# EEG_Schematic.net
KiCad netlist of a schematic drawn in Altium Designer
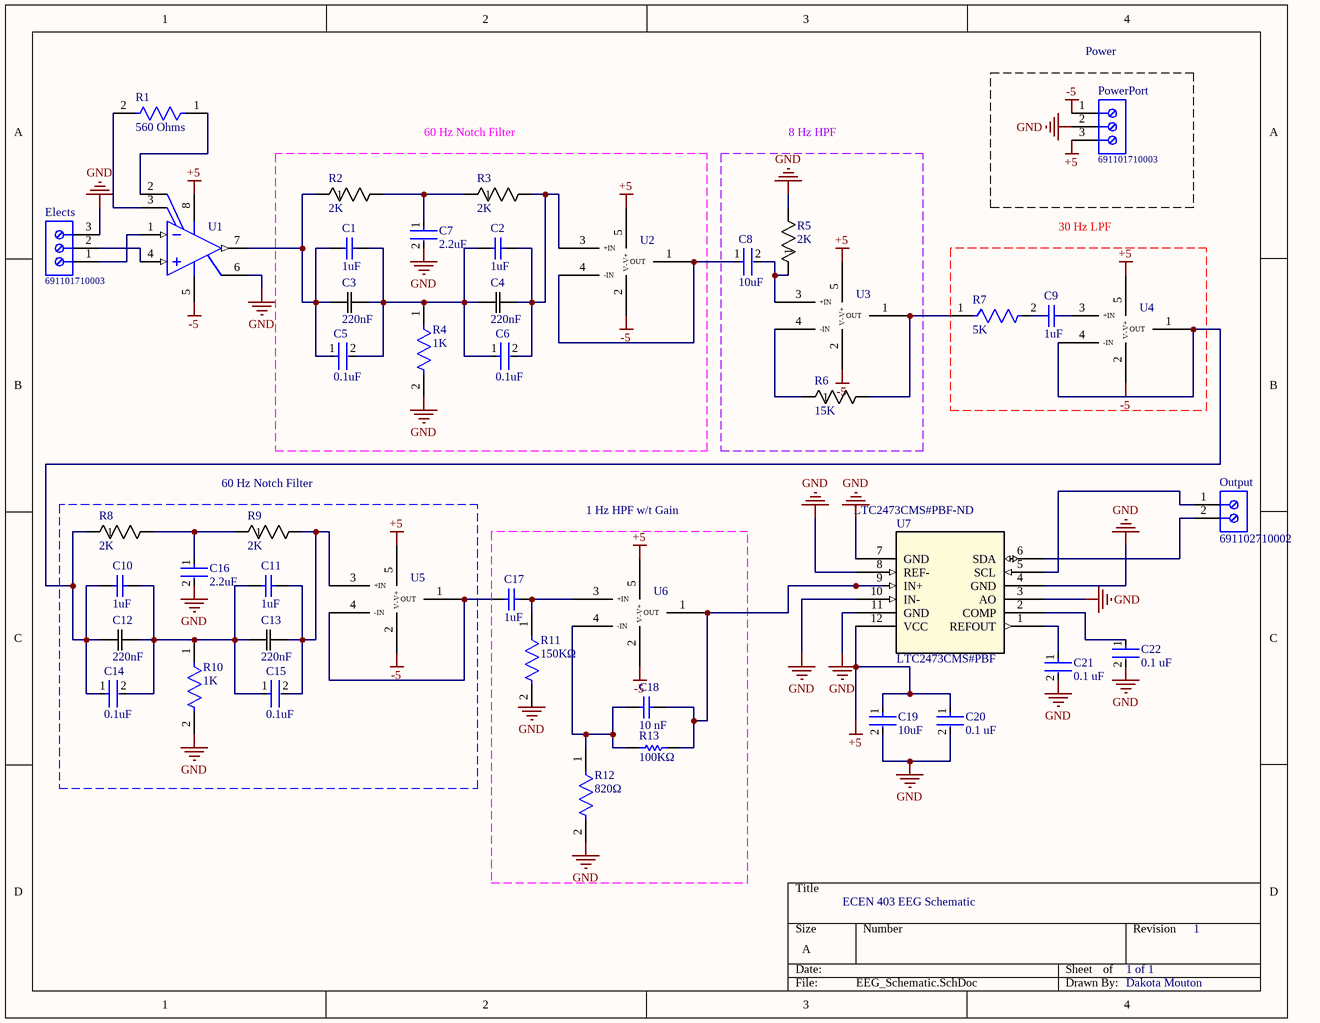
[diagram p0: EEG_Schematic.SchDoc]

(export (version "E")
  (design (tool "Eeschema 10.0.6"))
  (components
    (comp (ref "C1")
      (value "1uF")
      (footprint "CAPC1608X90X35LL15T15")
      (fields (field (name "PART NUMBER") "C0603C105K9PACTU") (field (name "MANUFACTURER") "Kemet"))
      (libsource (lib "Altium Content Vault") (part "CAP"))
    )
    (comp (ref "C2")
      (value "1uF")
      (footprint "CAPC1608X90X35LL15T15")
      (fields (field (name "PART NUMBER") "C0603C105K9PACTU") (field (name "MANUFACTURER") "Kemet"))
      (libsource (lib "Altium Content Vault") (part "CAP"))
    )
    (comp (ref "C3")
      (value "220nF")
      (footprint "CAP_CL05_SAM")
      (description "No Description Available")
      (fields
        (field (name "MANUFACTURER_PART_NUMBER") "CL05B224KO5NNNC")
        (field (name "COPYRIGHT") "Copyright (C) 2021 Ultra Librarian. All rights reserved.")
      )
      (libsource (lib "CL05B224KO5NNNC") (part "CL05B224KO5NNNC"))
    )
    (comp (ref "C4")
      (value "220nF")
      (footprint "CAP_CL05_SAM")
      (description "No Description Available")
      (fields
        (field (name "MANUFACTURER_PART_NUMBER") "CL05B224KO5NNNC")
        (field (name "COPYRIGHT") "Copyright (C) 2021 Ultra Librarian. All rights reserved.")
      )
      (libsource (lib "CL05B224KO5NNNC") (part "CL05B224KO5NNNC"))
    )
    (comp (ref "C5")
      (value "0.1uF")
      (footprint "FP-CL278-IPC_C")
      (description "Cap Ceramic 100nF 25V X5R ±10% SMD 0402 +85°C Paper T/R")
      (fields (field (name "VOLTAGE") "25V") (field (name "TOLERANCE") "10%"))
      (libsource (lib "Altium Content Vault") (part "b4654b650e69147ec39a6b967a45e02"))
    )
    (comp (ref "C6")
      (value "0.1uF")
      (footprint "FP-CL278-IPC_C")
      (description "Cap Ceramic 100nF 25V X5R ±10% SMD 0402 +85°C Paper T/R")
      (fields (field (name "VOLTAGE") "25V") (field (name "TOLERANCE") "10%"))
      (libsource (lib "Altium Content Vault") (part "b4654b650e69147ec39a6b967a45e02"))
    )
    (comp (ref "C7")
      (value "2.2uF")
      (footprint "FP-CL10-IPC_A")
      (description "Cap Ceramic 2.2uF 10V X7R ±10% Pad SMD 0603 +125°C T/R")
      (fields (field (name "TOLERANCE") "10%"))
      (libsource (lib "Altium Content Vault") (part "b4654b650e69147ec39a6b967a45e02"))
    )
    (comp (ref "C8")
      (value "10uF")
      (footprint "FP-CL21-IPC_C")
      (description "CL21 Series 0805 10uF 10V ±10% Tolerance X5R Multilayer Ceramic Chip Capacitor")
      (fields (field (name "TOLERANCE") "10%"))
      (libsource (lib "Altium Content Vault") (part "b4654b650e69147ec39a6b967a45e02"))
    )
    (comp (ref "C9")
      (value "1uF")
      (footprint "CAPC1608X90X35LL15T15")
      (fields (field (name "PART NUMBER") "C0603C105K9PACTU") (field (name "MANUFACTURER") "Kemet"))
      (libsource (lib "Altium Content Vault") (part "CAP"))
    )
    (comp (ref "C10")
      (value "1uF")
      (footprint "CAPC1608X90X35LL15T15")
      (fields (field (name "PART NUMBER") "C0603C105K9PACTU") (field (name "MANUFACTURER") "Kemet"))
      (libsource (lib "Altium Content Vault") (part "CAP"))
    )
    (comp (ref "C11")
      (value "1uF")
      (footprint "CAPC1608X90X35LL15T15")
      (fields (field (name "PART NUMBER") "C0603C105K9PACTU") (field (name "MANUFACTURER") "Kemet"))
      (libsource (lib "Altium Content Vault") (part "CAP"))
    )
    (comp (ref "C12")
      (value "220nF")
      (footprint "CAP_CL05_SAM")
      (description "No Description Available")
      (fields
        (field (name "MANUFACTURER_PART_NUMBER") "CL05B224KO5NNNC")
        (field (name "COPYRIGHT") "Copyright (C) 2021 Ultra Librarian. All rights reserved.")
      )
      (libsource (lib "CL05B224KO5NNNC") (part "CL05B224KO5NNNC"))
    )
    (comp (ref "C13")
      (value "220nF")
      (footprint "CAP_CL05_SAM")
      (description "No Description Available")
      (fields
        (field (name "MANUFACTURER_PART_NUMBER") "CL05B224KO5NNNC")
        (field (name "COPYRIGHT") "Copyright (C) 2021 Ultra Librarian. All rights reserved.")
      )
      (libsource (lib "CL05B224KO5NNNC") (part "CL05B224KO5NNNC"))
    )
    (comp (ref "C14")
      (value "0.1uF")
      (footprint "FP-CL278-IPC_C")
      (description "Cap Ceramic 100nF 25V X5R ±10% SMD 0402 +85°C Paper T/R")
      (fields (field (name "VOLTAGE") "25V") (field (name "TOLERANCE") "10%"))
      (libsource (lib "Altium Content Vault") (part "b4654b650e69147ec39a6b967a45e02"))
    )
    (comp (ref "C15")
      (value "0.1uF")
      (footprint "FP-CL278-IPC_C")
      (description "Cap Ceramic 100nF 25V X5R ±10% SMD 0402 +85°C Paper T/R")
      (fields (field (name "VOLTAGE") "25V") (field (name "TOLERANCE") "10%"))
      (libsource (lib "Altium Content Vault") (part "b4654b650e69147ec39a6b967a45e02"))
    )
    (comp (ref "C16")
      (value "2.2uF")
      (footprint "FP-CL10-IPC_A")
      (description "Cap Ceramic 2.2uF 10V X7R ±10% Pad SMD 0603 +125°C T/R")
      (fields (field (name "TOLERANCE") "10%"))
      (libsource (lib "Altium Content Vault") (part "b4654b650e69147ec39a6b967a45e02"))
    )
    (comp (ref "C17")
      (value "1uF")
      (footprint "CAPC1608X90X35LL15T15")
      (fields (field (name "PART NUMBER") "C0603C105K9PACTU") (field (name "MANUFACTURER") "Kemet"))
      (libsource (lib "Altium Content Vault") (part "CAP"))
    )
    (comp (ref "C18")
      (value "10 nF")
      (footprint "CAPC1005X56X25NL10T15")
      (fields
        (field (name "PART NUMBER") "0402YC103KAT2A")
        (field (name "MANUFACTURER") "AVX Interconnect / Elco")
      )
      (libsource (lib "Altium Content Vault") (part "CAP"))
    )
    (comp (ref "C19")
      (value "10uF")
      (footprint "FP-CL21-IPC_C")
      (description "CL21 Series 0805 10uF 10V ±10% Tolerance X5R Multilayer Ceramic Chip Capacitor")
      (fields (field (name "TOLERANCE") "10%"))
      (libsource (lib "Altium Content Vault") (part "b4654b650e69147ec39a6b967a45e02"))
    )
    (comp (ref "C20")
      (value "0.1 uF")
      (footprint "FP-CL278-IPC_C")
      (description "Cap Ceramic 100nF 25V X5R ±10% SMD 0402 +85°C Paper T/R")
      (fields (field (name "VOLTAGE") "25V") (field (name "TOLERANCE") "10%"))
      (libsource (lib "Altium Content Vault") (part "b4654b650e69147ec39a6b967a45e02"))
    )
    (comp (ref "C21")
      (value "0.1 uF")
      (footprint "FP-CL278-IPC_C")
      (description "Cap Ceramic 100nF 25V X5R ±10% SMD 0402 +85°C Paper T/R")
      (fields (field (name "VOLTAGE") "25V") (field (name "TOLERANCE") "10%"))
      (libsource (lib "Altium Content Vault") (part "b4654b650e69147ec39a6b967a45e02"))
    )
    (comp (ref "C22")
      (value "0.1 uF")
      (footprint "FP-CL278-IPC_C")
      (description "Cap Ceramic 100nF 25V X5R ±10% SMD 0402 +85°C Paper T/R")
      (fields (field (name "VOLTAGE") "25V") (field (name "TOLERANCE") "10%"))
      (libsource (lib "Altium Content Vault") (part "b4654b650e69147ec39a6b967a45e02"))
    )
    (comp (ref "Elects")
      (value "691101710003")
      (footprint "691101710003")
      (description "Series 101 - 5.00 mm Horizontal Entry Modular with Pressure Clamp WR-TBL, 3 pin")
      (fields (field (name "MANUFACTURER") "Wurth Elektronik") (field (name "PUBLISHER") "WurthElektronik"))
      (libsource (lib "Altium Content Vault") (part "WE-CN-1P-F-TB3"))
    )
    (comp (ref "Output")
      (value "691102710002")
      (footprint "691102710002")
      (description "Series 102 - 5.00 mm Horizontal Entry Modular with Pressure Clamp WR-TBL, 2 pin")
      (fields (field (name "MANUFACTURER") "Wurth Elektronik") (field (name "PUBLISHER") "WurthElektronik"))
      (libsource (lib "Altium Content Vault") (part "WE-CN-1P-F-TB2"))
    )
    (comp (ref "PowerPort")
      (value "691101710003")
      (footprint "691101710003")
      (description "Series 101 - 5.00 mm Horizontal Entry Modular with Pressure Clamp WR-TBL, 3 pin")
      (fields (field (name "MANUFACTURER") "Wurth Elektronik") (field (name "PUBLISHER") "WurthElektronik"))
      (libsource (lib "Altium Content Vault") (part "WE-CN-1P-F-TB3"))
    )
    (comp (ref "R1")
      (value "560 Ohms")
      (footprint "FP-CRGCQ1206-IPC_C")
      (description "CRGCQ 1206 560R 1%")
      (fields
        (field (name "MANUFACTURER PART NUMBER") "CRGCQ1206F560R")
        (field (name "OCTOPART") "https://octopart.com/crgcq1206f560r-te+connectivity-91018289")
      )
      (libsource (lib "Altium Content Vault") (part "1029c3af85768c4190bb7ad29bc67b5"))
    )
    (comp (ref "R2")
      (value "2K")
      (footprint "STA_RNCP0805_STP")
      (description "No Description Available")
      (fields
        (field (name "MANUFACTURER_PART_NUMBER") "RNCP0805FTD2K00")
        (field (name "COPYRIGHT") "Copyright (C) 2021 Ultra Librarian. All rights reserved.")
      )
      (libsource (lib "RNCP0805FTD2K00") (part "RNCP0805FTD2K00"))
    )
    (comp (ref "R3")
      (value "2K")
      (footprint "STA_RNCP0805_STP")
      (description "No Description Available")
      (fields
        (field (name "MANUFACTURER_PART_NUMBER") "RNCP0805FTD2K00")
        (field (name "COPYRIGHT") "Copyright (C) 2021 Ultra Librarian. All rights reserved.")
      )
      (libsource (lib "RNCP0805FTD2K00") (part "RNCP0805FTD2K00"))
    )
    (comp (ref "R4")
      (value "1K")
      (footprint "FP-RNCP0805-MFG")
      (description "1kΩ ±1% 0.25W 0805 High Power Anti-Sulfur Thin Film Chip Resistor")
      (fields (field (name "TOLERANCE") "1%"))
      (libsource (lib "Altium Content Vault") (part "1029c3af85768c4190bb7ad29bc67b5"))
    )
    (comp (ref "R5")
      (value "2K")
      (footprint "STA_RNCP0805_STP")
      (description "No Description Available")
      (fields
        (field (name "MANUFACTURER_PART_NUMBER") "RNCP0805FTD2K00")
        (field (name "COPYRIGHT") "Copyright (C) 2021 Ultra Librarian. All rights reserved.")
      )
      (libsource (lib "RNCP0805FTD2K00") (part "RNCP0805FTD2K00"))
    )
    (comp (ref "R6")
      (value "15K")
      (footprint "STA_RNCP0805_STP")
      (description "No Description Available")
      (fields
        (field (name "MANUFACTURER_PART_NUMBER") "RNCP0805FTD15K0")
        (field (name "COPYRIGHT") "Copyright (C) 2021 Ultra Librarian. All rights reserved.")
      )
      (libsource (lib "RNCP0805FTD15K0") (part "RNCP0805FTD15K0"))
    )
    (comp (ref "R7")
      (value "5K")
      (footprint "FP-RT1206-0_65-MFG")
      (description "RES SMD 5K OHM 0.1% 1/4W 1206")
      (fields
        (field (name "OCTOPART") "https://octopart.com/rt1206brd075kl-yageo-29806230")
        (field (name "MANUFACTURER") "Yageo")
      )
      (libsource (lib "Altium Content Vault") (part "1029c3af85768c4190bb7ad29bc67b5"))
    )
    (comp (ref "R8")
      (value "2K")
      (footprint "STA_RNCP0805_STP")
      (description "No Description Available")
      (fields
        (field (name "MANUFACTURER_PART_NUMBER") "RNCP0805FTD2K00")
        (field (name "COPYRIGHT") "Copyright (C) 2021 Ultra Librarian. All rights reserved.")
      )
      (libsource (lib "RNCP0805FTD2K00") (part "RNCP0805FTD2K00"))
    )
    (comp (ref "R9")
      (value "2K")
      (footprint "STA_RNCP0805_STP")
      (description "No Description Available")
      (fields
        (field (name "MANUFACTURER_PART_NUMBER") "RNCP0805FTD2K00")
        (field (name "COPYRIGHT") "Copyright (C) 2021 Ultra Librarian. All rights reserved.")
      )
      (libsource (lib "RNCP0805FTD2K00") (part "RNCP0805FTD2K00"))
    )
    (comp (ref "R10")
      (value "1K")
      (footprint "FP-RNCP0805-MFG")
      (description "1kΩ ±1% 0.25W 0805 High Power Anti-Sulfur Thin Film Chip Resistor")
      (fields (field (name "TOLERANCE") "1%"))
      (libsource (lib "Altium Content Vault") (part "1029c3af85768c4190bb7ad29bc67b5"))
    )
    (comp (ref "R11")
      (value "150KΩ")
      (footprint "FP-CRGP0603-IPC_C")
      (description "CRGP0603 150KΩ 0.25W ±100ppm/°C 1% 50V")
      (fields
        (field (name "TOLERANCE") "0.01")
        (field (name "OCTOPART") "https://octopart.com/crgp0603f150k-te+connectivity-91018727")
      )
      (libsource (lib "Altium Content Vault") (part "1029c3af85768c4190bb7ad29bc67b5"))
    )
    (comp (ref "R12")
      (value "820Ω")
      (footprint "FP-RMCF1206-IPC_C")
      (description "820Ω ±5% 0.25W 1206 Thick Film Chip Resistor AEC-Q200 compliant")
      (fields (field (name "TOLERANCE") "5%"))
      (libsource (lib "Altium Content Vault") (part "1029c3af85768c4190bb7ad29bc67b5"))
    )
    (comp (ref "R13")
      (value "100KΩ")
      (footprint "RESC2013X60X30NL20T20")
      (fields (field (name "MANUFACTURER") "KOA Speer") (field (name "PART NUMBER") "RK73H2ATTD1003F"))
      (libsource (lib "Altium Content Vault") (part "RES"))
    )
    (comp (ref "U1")
      (value "AD8221BRZ-R7 Instrumentation Amplifier")
      (footprint "ADI-R-8_M")
      (fields (field (name "MANUFACTURER") "Analog Devices") (field (name "PARTNUMBER") "AD8221BRZ-R7"))
      (libsource (lib "Altium Content Vault") (part "ADI-AD8221-8"))
    )
    (comp (ref "U2")
      (value "ADA4610-1ARJZ-R7")
      (footprint "RJ_5_ADI")
      (description "No Description Available")
      (fields (field (name "COPYRIGHT") "Copyright (C) 2021 Ultra Librarian. All rights reserved."))
      (libsource (lib "ADA4610-1ARJZ-R7") (part "ADA4610-1ARJZ-R7"))
    )
    (comp (ref "U3")
      (value "ADA4610-1ARJZ-R7")
      (footprint "RJ_5_ADI")
      (description "No Description Available")
      (fields (field (name "COPYRIGHT") "Copyright (C) 2021 Ultra Librarian. All rights reserved."))
      (libsource (lib "ADA4610-1ARJZ-R7") (part "ADA4610-1ARJZ-R7"))
    )
    (comp (ref "U4")
      (value "ADA4610-1ARJZ-R7")
      (footprint "RJ_5_ADI")
      (description "No Description Available")
      (fields (field (name "COPYRIGHT") "Copyright (C) 2021 Ultra Librarian. All rights reserved."))
      (libsource (lib "ADA4610-1ARJZ-R7") (part "ADA4610-1ARJZ-R7"))
    )
    (comp (ref "U5")
      (value "ADA4610-1ARJZ-R7")
      (footprint "RJ_5_ADI")
      (description "No Description Available")
      (fields (field (name "COPYRIGHT") "Copyright (C) 2021 Ultra Librarian. All rights reserved."))
      (libsource (lib "ADA4610-1ARJZ-R7") (part "ADA4610-1ARJZ-R7"))
    )
    (comp (ref "U6")
      (value "ADA4610-1ARJZ-R7")
      (footprint "RJ_5_ADI")
      (description "No Description Available")
      (fields (field (name "COPYRIGHT") "Copyright (C) 2021 Ultra Librarian. All rights reserved."))
      (libsource (lib "ADA4610-1ARJZ-R7") (part "ADA4610-1ARJZ-R7"))
    )
    (comp (ref "U7")
      (value "LTC2473CMS#PBF")
      (footprint "MSOP-12_MS_LIT")
      (description "No Description Available")
      (fields
        (field (name "SUPPLIER PART NUMBER 1") "LTC2473CMS#PBF-ND")
        (field (name "COPYRIGHT") "Copyright (C) 2021 Ultra Librarian. All rights reserved.")
      )
      (libsource (lib "LTC2473CMS&hash_PBF") (part "LTC2473CMS#PBF"))
    )
  )
  (nets
    (net (code "1") (name "+5") (class "Default")
      (node (ref "C19") (pin "1") (pinfunction "1_1") (pintype "passive"))
      (node (ref "C20") (pin "1") (pinfunction "1_1") (pintype "passive"))
      (node (ref "PowerPort") (pin "3") (pinfunction "3_3") (pintype "passive"))
      (node (ref "U1") (pin "8") (pinfunction "VS+_8") (pintype "power_in"))
      (node (ref "U2") (pin "5") (pinfunction "V+_5") (pintype "power_in"))
      (node (ref "U3") (pin "5") (pinfunction "V+_5") (pintype "power_in"))
      (node (ref "U4") (pin "5") (pinfunction "V+_5") (pintype "power_in"))
      (node (ref "U5") (pin "5") (pinfunction "V+_5") (pintype "power_in"))
      (node (ref "U6") (pin "5") (pinfunction "V+_5") (pintype "power_in"))
      (node (ref "U7") (pin "12") (pinfunction "VCC_12") (pintype "power_in"))
    )
    (net (code "2") (name "-5") (class "Default")
      (node (ref "PowerPort") (pin "1") (pinfunction "1_1") (pintype "passive"))
      (node (ref "U1") (pin "5") (pinfunction "VS-_5") (pintype "power_in"))
      (node (ref "U2") (pin "2") (pinfunction "V-_2") (pintype "power_in"))
      (node (ref "U3") (pin "2") (pinfunction "V-_2") (pintype "power_in"))
      (node (ref "U4") (pin "2") (pinfunction "V-_2") (pintype "power_in"))
      (node (ref "U5") (pin "2") (pinfunction "V-_2") (pintype "power_in"))
      (node (ref "U6") (pin "2") (pinfunction "V-_2") (pintype "power_in"))
    )
    (net (code "3") (name "GND") (class "Default")
      (node (ref "C16") (pin "2") (pinfunction "2_2") (pintype "passive"))
      (node (ref "C19") (pin "2") (pinfunction "2_2") (pintype "passive"))
      (node (ref "C20") (pin "2") (pinfunction "2_2") (pintype "passive"))
      (node (ref "C21") (pin "2") (pinfunction "2_2") (pintype "passive"))
      (node (ref "C22") (pin "2") (pinfunction "2_2") (pintype "passive"))
      (node (ref "C7") (pin "2") (pinfunction "2_2") (pintype "passive"))
      (node (ref "Elects") (pin "3") (pinfunction "3_3") (pintype "passive"))
      (node (ref "PowerPort") (pin "2") (pinfunction "2_2") (pintype "passive"))
      (node (ref "R10") (pin "2") (pinfunction "2_2") (pintype "passive"))
      (node (ref "R12") (pin "2") (pinfunction "2_2") (pintype "passive"))
      (node (ref "R4") (pin "2") (pinfunction "2_2") (pintype "passive"))
      (node (ref "R5") (pin "2") (pinfunction "2_2") (pintype "passive"))
      (node (ref "U1") (pin "6") (pinfunction "REF_6") (pintype "passive"))
      (node (ref "U7") (pin "10") (pinfunction "IN-_10") (pintype "input"))
      (node (ref "U7") (pin "11") (pinfunction "GND_11") (pintype "power_in"))
      (node (ref "U7") (pin "3") (pinfunction "AO_3") (pintype "passive"))
      (node (ref "U7") (pin "4") (pinfunction "GND_4") (pintype "power_in"))
      (node (ref "U7") (pin "7") (pinfunction "GND_7") (pintype "power_in"))
      (node (ref "U7") (pin "8") (pinfunction "REF-_8") (pintype "input"))
    )
    (net (code "4") (name "Net-(C1-Pad2)") (class "Default")
      (node (ref "C1") (pin "2") (pinfunction "2_2") (pintype "passive"))
      (node (ref "C2") (pin "1") (pinfunction "1_1") (pintype "passive"))
      (node (ref "C3") (pin "2") (pinfunction "2_2") (pintype "passive"))
      (node (ref "C4") (pin "1") (pinfunction "1_1") (pintype "passive"))
      (node (ref "C5") (pin "2") (pinfunction "2_2") (pintype "passive"))
      (node (ref "C6") (pin "1") (pinfunction "1_1") (pintype "passive"))
      (node (ref "R4") (pin "1") (pinfunction "1_1") (pintype "passive"))
    )
    (net (code "5") (name "Net-(C7-Pad1)") (class "Default")
      (node (ref "C7") (pin "1") (pinfunction "1_1") (pintype "passive"))
      (node (ref "R2") (pin "2") (pinfunction "2_2") (pintype "passive"))
      (node (ref "R3") (pin "1") (pinfunction "1_1") (pintype "passive"))
    )
    (net (code "6") (name "Net-(C9-Pad1)") (class "Default")
      (node (ref "C9") (pin "1") (pinfunction "1_1") (pintype "passive"))
      (node (ref "R7") (pin "2") (pinfunction "2_2") (pintype "passive"))
    )
    (net (code "7") (name "Net-(C10-Pad2)") (class "Default")
      (node (ref "C10") (pin "2") (pinfunction "2_2") (pintype "passive"))
      (node (ref "C11") (pin "1") (pinfunction "1_1") (pintype "passive"))
      (node (ref "C12") (pin "2") (pinfunction "2_2") (pintype "passive"))
      (node (ref "C13") (pin "1") (pinfunction "1_1") (pintype "passive"))
      (node (ref "C14") (pin "2") (pinfunction "2_2") (pintype "passive"))
      (node (ref "C15") (pin "1") (pinfunction "1_1") (pintype "passive"))
      (node (ref "R10") (pin "1") (pinfunction "1_1") (pintype "passive"))
    )
    (net (code "8") (name "Net-(C16-Pad1)") (class "Default")
      (node (ref "C16") (pin "1") (pinfunction "1_1") (pintype "passive"))
      (node (ref "R8") (pin "2") (pinfunction "2_2") (pintype "passive"))
      (node (ref "R9") (pin "1") (pinfunction "1_1") (pintype "passive"))
    )
    (net (code "9") (name "Net-(R1-Pad1)") (class "Default")
      (node (ref "R1") (pin "1") (pinfunction "1_1") (pintype "passive"))
      (node (ref "U1") (pin "2") (pinfunction "RG_2") (pintype "passive"))
    )
    (net (code "10") (name "Net-(R1-Pad2)") (class "Default")
      (node (ref "R1") (pin "2") (pinfunction "2_2") (pintype "passive"))
      (node (ref "U1") (pin "3") (pinfunction "RG_3") (pintype "passive"))
    )
    (net (code "11") (name "Net-(U1-IN+)") (class "Default")
      (node (ref "Elects") (pin "2") (pinfunction "2_2") (pintype "passive"))
      (node (ref "U1") (pin "4") (pinfunction "IN+_4") (pintype "input"))
    )
    (net (code "12") (name "Net-(U1-IN-)") (class "Default")
      (node (ref "Elects") (pin "1") (pinfunction "1_1") (pintype "passive"))
      (node (ref "U1") (pin "1") (pinfunction "IN-_1") (pintype "input"))
    )
    (net (code "13") (name "Net-(U1-VOUT)") (class "Default")
      (node (ref "C1") (pin "1") (pinfunction "1_1") (pintype "passive"))
      (node (ref "C3") (pin "1") (pinfunction "1_1") (pintype "passive"))
      (node (ref "C5") (pin "1") (pinfunction "1_1") (pintype "passive"))
      (node (ref "R2") (pin "1") (pinfunction "1_1") (pintype "passive"))
      (node (ref "U1") (pin "7") (pinfunction "VOUT_7") (pintype "output"))
    )
    (net (code "14") (name "Net-(U2-+IN)") (class "Default")
      (node (ref "C2") (pin "2") (pinfunction "2_2") (pintype "passive"))
      (node (ref "C4") (pin "2") (pinfunction "2_2") (pintype "passive"))
      (node (ref "C6") (pin "2") (pinfunction "2_2") (pintype "passive"))
      (node (ref "R3") (pin "2") (pinfunction "2_2") (pintype "passive"))
      (node (ref "U2") (pin "3") (pinfunction "+IN_3") (pintype "passive"))
    )
    (net (code "15") (name "Net-(U2--IN)") (class "Default")
      (node (ref "C8") (pin "1") (pinfunction "1_1") (pintype "passive"))
      (node (ref "U2") (pin "1") (pinfunction "OUT_1") (pintype "passive"))
      (node (ref "U2") (pin "4") (pinfunction "-IN_4") (pintype "passive"))
    )
    (net (code "16") (name "Net-(U3-+IN)") (class "Default")
      (node (ref "C8") (pin "2") (pinfunction "2_2") (pintype "passive"))
      (node (ref "R5") (pin "1") (pinfunction "1_1") (pintype "passive"))
      (node (ref "U3") (pin "3") (pinfunction "+IN_3") (pintype "passive"))
    )
    (net (code "17") (name "Net-(U3--IN)") (class "Default")
      (node (ref "R6") (pin "1") (pinfunction "1_1") (pintype "passive"))
      (node (ref "U3") (pin "4") (pinfunction "-IN_4") (pintype "passive"))
    )
    (net (code "18") (name "Net-(U3-OUT)") (class "Default")
      (node (ref "R6") (pin "2") (pinfunction "2_2") (pintype "passive"))
      (node (ref "R7") (pin "1") (pinfunction "1_1") (pintype "passive"))
      (node (ref "U3") (pin "1") (pinfunction "OUT_1") (pintype "passive"))
    )
    (net (code "19") (name "Net-(U4-+IN)") (class "Default")
      (node (ref "C9") (pin "2") (pinfunction "2_2") (pintype "passive"))
      (node (ref "U4") (pin "3") (pinfunction "+IN_3") (pintype "passive"))
    )
    (net (code "20") (name "Net-(U4--IN)") (class "Default")
      (node (ref "C10") (pin "1") (pinfunction "1_1") (pintype "passive"))
      (node (ref "C12") (pin "1") (pinfunction "1_1") (pintype "passive"))
      (node (ref "C14") (pin "1") (pinfunction "1_1") (pintype "passive"))
      (node (ref "R8") (pin "1") (pinfunction "1_1") (pintype "passive"))
      (node (ref "U4") (pin "1") (pinfunction "OUT_1") (pintype "passive"))
      (node (ref "U4") (pin "4") (pinfunction "-IN_4") (pintype "passive"))
    )
    (net (code "21") (name "Net-(U5-+IN)") (class "Default")
      (node (ref "C11") (pin "2") (pinfunction "2_2") (pintype "passive"))
      (node (ref "C13") (pin "2") (pinfunction "2_2") (pintype "passive"))
      (node (ref "C15") (pin "2") (pinfunction "2_2") (pintype "passive"))
      (node (ref "R9") (pin "2") (pinfunction "2_2") (pintype "passive"))
      (node (ref "U5") (pin "3") (pinfunction "+IN_3") (pintype "passive"))
    )
    (net (code "22") (name "Net-(U5--IN)") (class "Default")
      (node (ref "C17") (pin "1") (pinfunction "1_1") (pintype "passive"))
      (node (ref "U5") (pin "1") (pinfunction "OUT_1") (pintype "passive"))
      (node (ref "U5") (pin "4") (pinfunction "-IN_4") (pintype "passive"))
    )
    (net (code "23") (name "Net-(U6-+IN)") (class "Default")
      (node (ref "C17") (pin "2") (pinfunction "2_2") (pintype "passive"))
      (node (ref "R11") (pin "1") (pinfunction "1_1") (pintype "passive"))
      (node (ref "U6") (pin "3") (pinfunction "+IN_3") (pintype "passive"))
    )
    (net (code "24") (name "Net-(U6--IN)") (class "Default")
      (node (ref "C18") (pin "1") (pinfunction "1_1") (pintype "passive"))
      (node (ref "R12") (pin "1") (pinfunction "1_1") (pintype "passive"))
      (node (ref "R13") (pin "1") (pinfunction "1_1") (pintype "passive"))
      (node (ref "U6") (pin "4") (pinfunction "-IN_4") (pintype "passive"))
    )
    (net (code "25") (name "Net-(U6-OUT)") (class "Default")
      (node (ref "C18") (pin "2") (pinfunction "2_2") (pintype "passive"))
      (node (ref "R13") (pin "2") (pinfunction "2_2") (pintype "passive"))
      (node (ref "U6") (pin "1") (pinfunction "OUT_1") (pintype "passive"))
      (node (ref "U7") (pin "9") (pinfunction "IN+_9") (pintype "input"))
    )
    (net (code "26") (name "Net-(U7-COMP)") (class "Default")
      (node (ref "C22") (pin "1") (pinfunction "1_1") (pintype "passive"))
      (node (ref "U7") (pin "2") (pinfunction "COMP_2") (pintype "passive"))
    )
    (net (code "27") (name "Net-(U7-REFOUT)") (class "Default")
      (node (ref "C21") (pin "1") (pinfunction "1_1") (pintype "passive"))
      (node (ref "U7") (pin "1") (pinfunction "REFOUT_1") (pintype "output"))
    )
    (net (code "28") (name "Net-(U7-SCL)") (class "Default")
      (node (ref "Output") (pin "1") (pinfunction "1_1") (pintype "passive"))
      (node (ref "U7") (pin "5") (pinfunction "SCL_5") (pintype "input"))
    )
    (net (code "29") (name "Net-(U7-SDA)") (class "Default")
      (node (ref "Output") (pin "2") (pinfunction "2_2") (pintype "passive"))
      (node (ref "U7") (pin "6") (pinfunction "SDA_6") (pintype "bidirectional"))
    )
    (net (code "30") (name "unconnected-(R11-Pad2)") (class "Default")
      (node (ref "R11") (pin "2") (pinfunction "2_2") (pintype "passive"))
    )
  )
)
